# Knob_8266.net
KiCad netlist of a schematic drawn in EAGLE
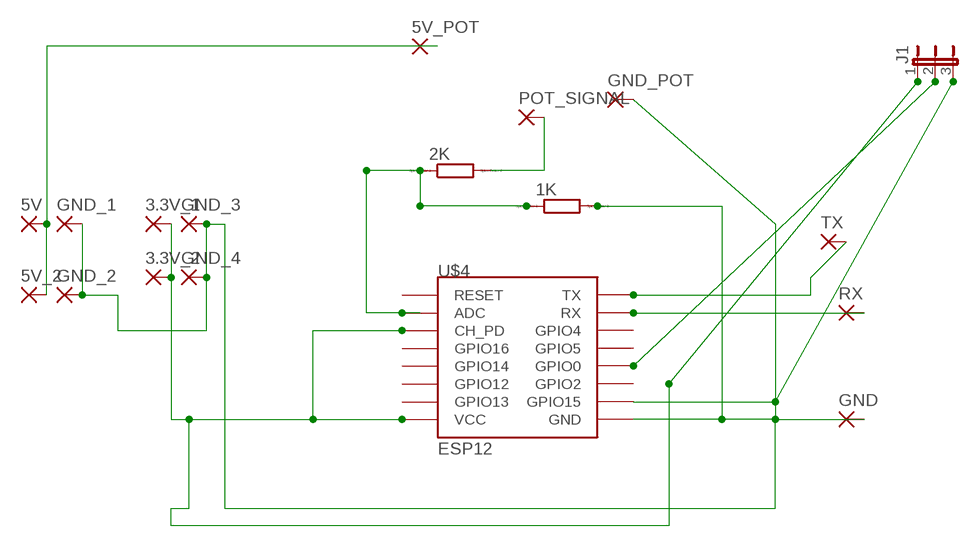
[diagram p0: schematic, sheet 1]

(export (version "E")
  (design (tool "Eeschema 10.0.6"))
  (components
    (comp (ref "1K")
      (value "R0204/7")
      (footprint "eagle-import:0204_7")
      (libsource (lib "eagle-import") (part "R0204/7"))
    )
    (comp (ref "2K")
      (value "R0204/7")
      (footprint "eagle-import:0204_7")
      (libsource (lib "eagle-import") (part "R0204/7"))
    )
    (comp (ref "3.3V_1")
      (value "2,15/1,0")
      (footprint "eagle-import:2,15_1,0")
      (libsource (lib "eagle-import") (part "2,15/1,0"))
    )
    (comp (ref "3.3V_2")
      (value "2,15/1,0")
      (footprint "eagle-import:2,15_1,0")
      (libsource (lib "eagle-import") (part "2,15/1,0"))
    )
    (comp (ref "5V")
      (value "2,15/1,0")
      (footprint "eagle-import:2,15_1,0")
      (libsource (lib "eagle-import") (part "2,15/1,0"))
    )
    (comp (ref "5V_2")
      (value "2,15/1,0")
      (footprint "eagle-import:2,15_1,0")
      (libsource (lib "eagle-import") (part "2,15/1,0"))
    )
    (comp (ref "5V_POT")
      (value "2,15/1,0")
      (footprint "eagle-import:2,15_1,0")
      (libsource (lib "eagle-import") (part "2,15/1,0"))
    )
    (comp (ref "GND")
      (value "2,15/1,0")
      (footprint "eagle-import:2,15_1,0")
      (libsource (lib "eagle-import") (part "2,15/1,0"))
    )
    (comp (ref "GND_1")
      (value "2,15/1,0")
      (footprint "eagle-import:2,15_1,0")
      (libsource (lib "eagle-import") (part "2,15/1,0"))
    )
    (comp (ref "GND_2")
      (value "2,15/1,0")
      (footprint "eagle-import:2,15_1,0")
      (libsource (lib "eagle-import") (part "2,15/1,0"))
    )
    (comp (ref "GND_3")
      (value "2,15/1,0")
      (footprint "eagle-import:2,15_1,0")
      (libsource (lib "eagle-import") (part "2,15/1,0"))
    )
    (comp (ref "GND_4")
      (value "2,15/1,0")
      (footprint "eagle-import:2,15_1,0")
      (libsource (lib "eagle-import") (part "2,15/1,0"))
    )
    (comp (ref "GND_POT")
      (value "2,15/1,0")
      (footprint "eagle-import:2,15_1,0")
      (libsource (lib "eagle-import") (part "2,15/1,0"))
    )
    (comp (ref "J1")
      (value "JP2E")
      (footprint "eagle-import:JP2")
      (libsource (lib "eagle-import") (part "JP2E"))
    )
    (comp (ref "POT_SIGNAL")
      (value "2,15/1,0")
      (footprint "eagle-import:2,15_1,0")
      (libsource (lib "eagle-import") (part "2,15/1,0"))
    )
    (comp (ref "RX")
      (value "2,15/1,0")
      (footprint "eagle-import:2,15_1,0")
      (libsource (lib "eagle-import") (part "2,15/1,0"))
    )
    (comp (ref "TX")
      (value "2,15/1,0")
      (footprint "eagle-import:2,15_1,0")
      (libsource (lib "eagle-import") (part "2,15/1,0"))
    )
    (comp (ref "U$4")
      (value "ESP12")
      (footprint "eagle-import:ESP12")
      (libsource (lib "eagle-import") (part "ESP12"))
    )
  )
  (nets
    (net (code "1") (name "/5V") (class "Default")
      (node (ref "1K") (pin "2") (pinfunction "2_2") (pintype "passive"))
      (node (ref "5V") (pin "1") (pinfunction "P_1") (pintype "passive"))
      (node (ref "5V_2") (pin "1") (pinfunction "P_1") (pintype "passive"))
      (node (ref "5V_POT") (pin "1") (pinfunction "P_1") (pintype "passive"))
      (node (ref "GND") (pin "1") (pinfunction "P_1") (pintype "passive"))
      (node (ref "GND_1") (pin "1") (pinfunction "P_1") (pintype "passive"))
      (node (ref "GND_2") (pin "1") (pinfunction "P_1") (pintype "passive"))
      (node (ref "GND_3") (pin "1") (pinfunction "P_1") (pintype "passive"))
      (node (ref "GND_4") (pin "1") (pinfunction "P_1") (pintype "passive"))
      (node (ref "GND_POT") (pin "1") (pinfunction "P_1") (pintype "passive"))
      (node (ref "J1") (pin "3") (pinfunction "3_3") (pintype "passive"))
      (node (ref "U$4") (pin "GND") (pinfunction "GND_GND") (pintype "bidirectional"))
      (node (ref "U$4") (pin "GPIO15") (pinfunction "GPIO15_GPIO15") (pintype "bidirectional"))
    )
    (net (code "2") (name "Net-(1K-Pad1)") (class "Default")
      (node (ref "1K") (pin "1") (pinfunction "1_1") (pintype "passive"))
      (node (ref "2K") (pin "1") (pinfunction "1_1") (pintype "passive"))
      (node (ref "U$4") (pin "ADC") (pinfunction "ADC_ADC") (pintype "bidirectional"))
    )
    (net (code "3") (name "Net-(3.3V_1-P)") (class "Default")
      (node (ref "3.3V_1") (pin "1") (pinfunction "P_1") (pintype "passive"))
      (node (ref "3.3V_2") (pin "1") (pinfunction "P_1") (pintype "passive"))
      (node (ref "J1") (pin "1") (pinfunction "1_1") (pintype "passive"))
      (node (ref "U$4") (pin "CH_PD") (pinfunction "CH_PD_CH_PD") (pintype "bidirectional"))
      (node (ref "U$4") (pin "VCC") (pinfunction "VCC_VCC") (pintype "bidirectional"))
    )
    (net (code "4") (name "Net-(J1-Pad2)") (class "Default")
      (node (ref "J1") (pin "2") (pinfunction "2_2") (pintype "passive"))
      (node (ref "U$4") (pin "GPIO0") (pinfunction "GPIO0_GPIO0") (pintype "bidirectional"))
    )
    (net (code "5") (name "Net-(POT_SIGNAL-P)") (class "Default")
      (node (ref "2K") (pin "2") (pinfunction "2_2") (pintype "passive"))
      (node (ref "POT_SIGNAL") (pin "1") (pinfunction "P_1") (pintype "passive"))
    )
    (net (code "6") (name "Net-(RX-P)") (class "Default")
      (node (ref "RX") (pin "1") (pinfunction "P_1") (pintype "passive"))
      (node (ref "U$4") (pin "RX") (pinfunction "RX_RX") (pintype "bidirectional"))
    )
    (net (code "7") (name "Net-(TX-P)") (class "Default")
      (node (ref "TX") (pin "1") (pinfunction "P_1") (pintype "passive"))
      (node (ref "U$4") (pin "TX") (pinfunction "TX_TX") (pintype "bidirectional"))
    )
    (net (code "8") (name "unconnected-(U$4-PadGPIO2)") (class "Default")
      (node (ref "U$4") (pin "GPIO2") (pinfunction "GPIO2_GPIO2") (pintype "bidirectional"))
    )
    (net (code "9") (name "unconnected-(U$4-PadGPIO4)") (class "Default")
      (node (ref "U$4") (pin "GPIO4") (pinfunction "GPIO4_GPIO4") (pintype "bidirectional"))
    )
    (net (code "10") (name "unconnected-(U$4-PadGPIO5)") (class "Default")
      (node (ref "U$4") (pin "GPIO5") (pinfunction "GPIO5_GPIO5") (pintype "bidirectional"))
    )
    (net (code "11") (name "unconnected-(U$4-PadGPIO12)") (class "Default")
      (node (ref "U$4") (pin "GPIO12") (pinfunction "GPIO12_GPIO12") (pintype "bidirectional"))
    )
    (net (code "12") (name "unconnected-(U$4-PadGPIO13)") (class "Default")
      (node (ref "U$4") (pin "GPIO13") (pinfunction "GPIO13_GPIO13") (pintype "bidirectional"))
    )
    (net (code "13") (name "unconnected-(U$4-PadGPIO14)") (class "Default")
      (node (ref "U$4") (pin "GPIO14") (pinfunction "GPIO14_GPIO14") (pintype "bidirectional"))
    )
    (net (code "14") (name "unconnected-(U$4-PadGPIO16)") (class "Default")
      (node (ref "U$4") (pin "GPIO16") (pinfunction "GPIO16_GPIO16") (pintype "bidirectional"))
    )
    (net (code "15") (name "unconnected-(U$4-PadRESET)") (class "Default")
      (node (ref "U$4") (pin "RESET") (pinfunction "RESET_RESET") (pintype "bidirectional"))
    )
  )
)
